# S01-INTERFACES.net
KiCad netlist of a schematic drawn in Altium Designer
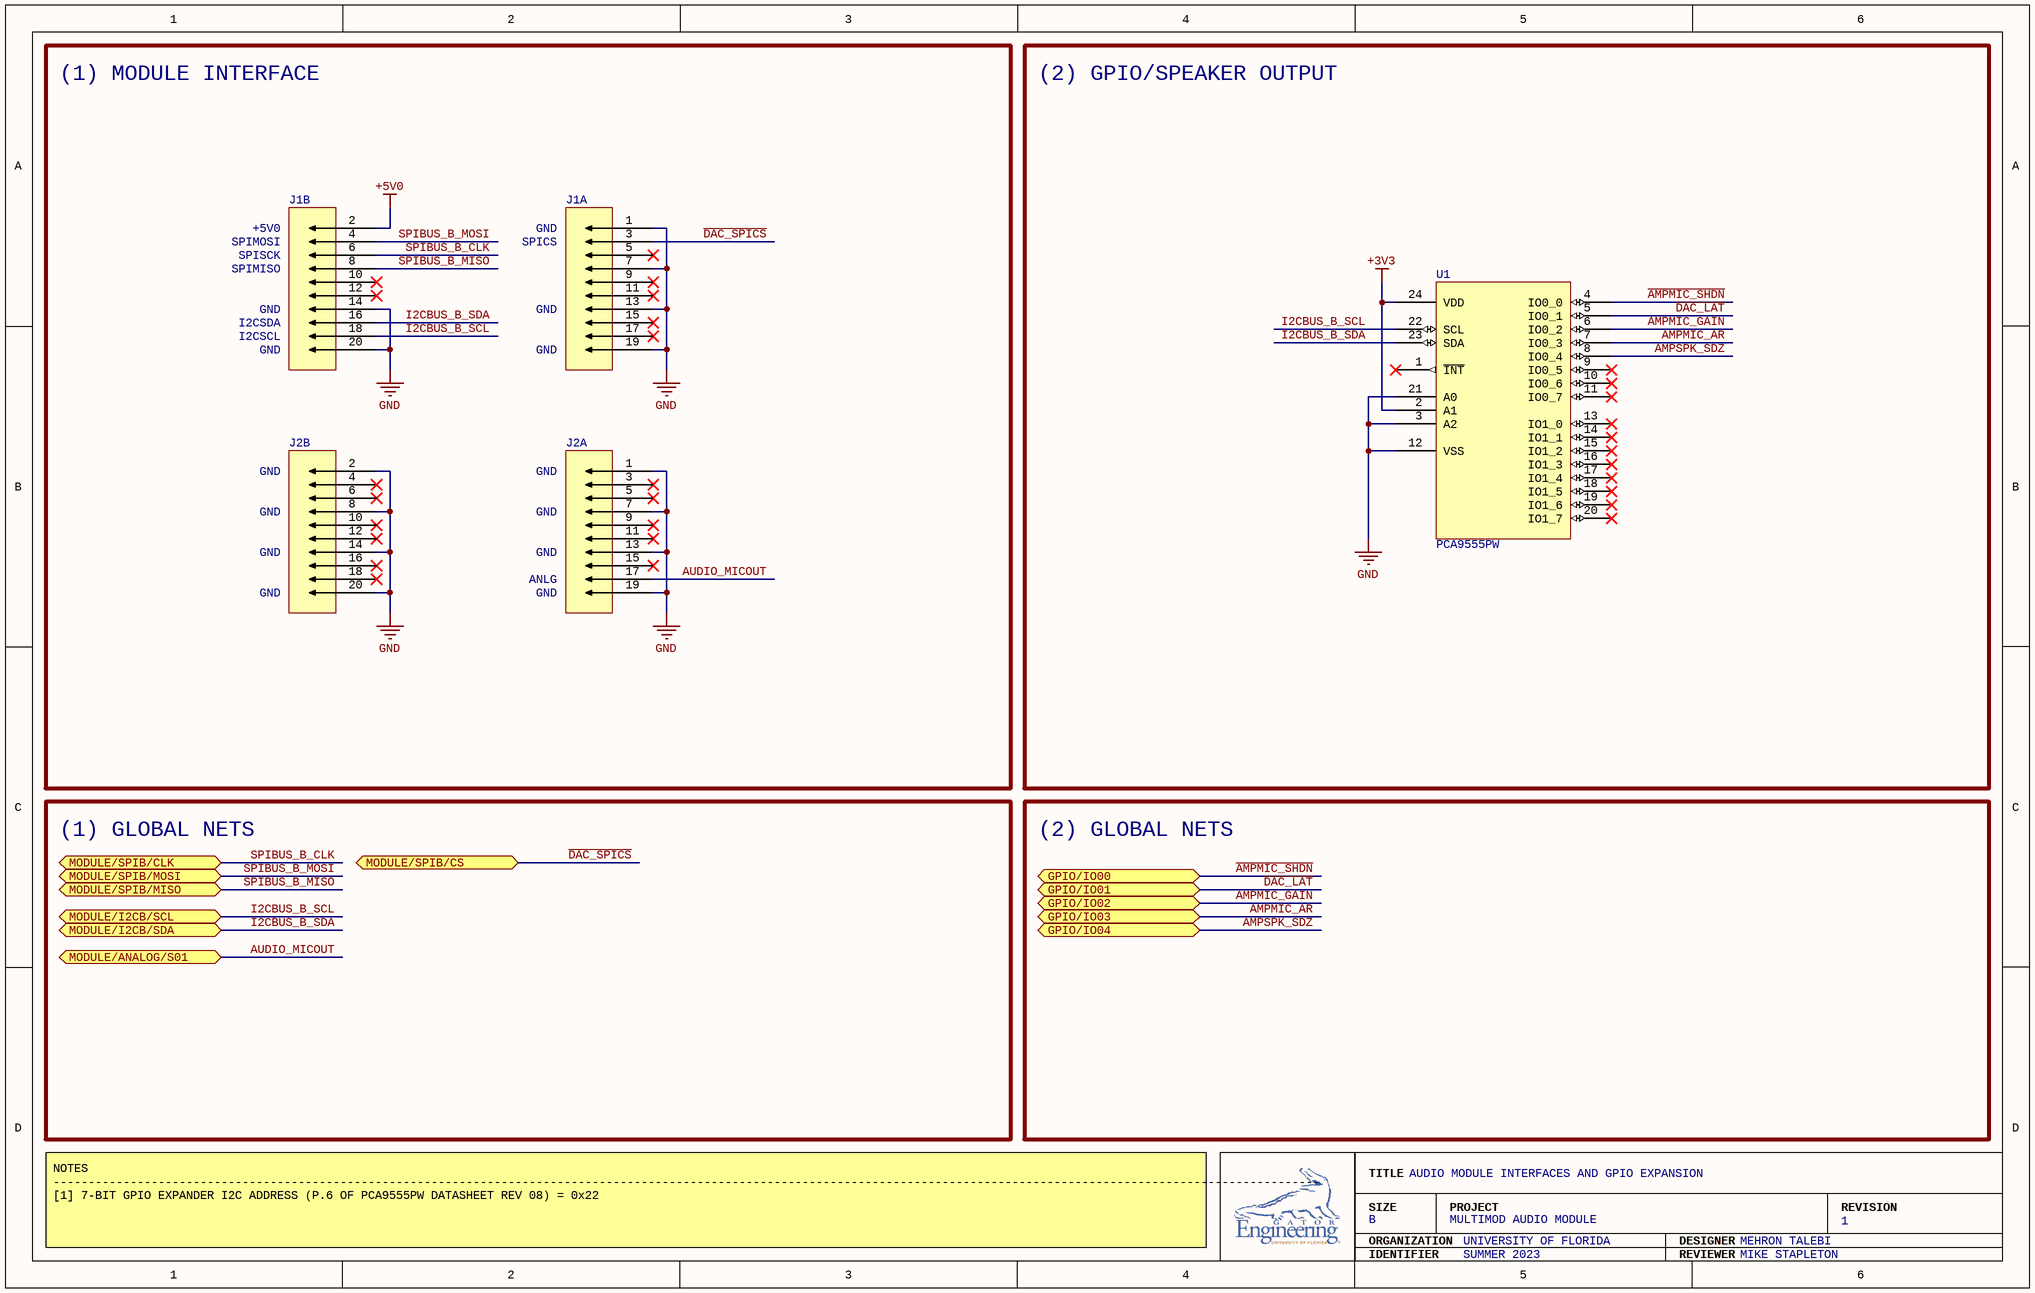
[diagram p0: S01-INTERFACES.SchDoc]

(export (version "E")
  (design (tool "Eeschema 10.0.6"))
  (components
    (comp (ref "J1")
      (value "NPTC102KFMS-RC")
      (footprint "NPTC102KFMS-RC")
      (description "CONN HDR 20POS 0.1 TIN SMD")
      (libsource (lib "Master") (part "NPTC102KFMS-RC"))
    )
    (comp (ref "J2")
      (value "NPTC102KFMS-RC")
      (footprint "NPTC102KFMS-RC")
      (description "CONN HDR 20POS 0.1 TIN SMD")
      (libsource (lib "Master") (part "NPTC102KFMS-RC"))
    )
    (comp (ref "U1")
      (value "PCA9555PW")
      (footprint "PCA9555PW")
      (description "IC XPND 400KHZ I2C SMBUS 24TSSOP")
      (libsource (lib "Master") (part "PCA9555PW"))
    )
  )
  (nets
    (net (code "1") (name "+3V3") (class "Default")
      (node (ref "U1") (pin "2") (pinfunction "A1_2") (pintype "passive"))
      (node (ref "U1") (pin "24") (pinfunction "VDD_24") (pintype "power_in"))
    )
    (net (code "2") (name "+5V0") (class "Default")
      (node (ref "J1") (pin "2") (pinfunction "2_2") (pintype "passive"))
    )
    (net (code "3") (name "/AMPMIC_AR") (class "Default")
      (node (ref "U1") (pin "7") (pinfunction "IO0_3_7") (pintype "bidirectional"))
    )
    (net (code "4") (name "/AMPMIC_GAIN") (class "Default")
      (node (ref "U1") (pin "6") (pinfunction "IO0_2_6") (pintype "bidirectional"))
    )
    (net (code "5") (name "/AMPMIC_SHDN") (class "Default")
      (node (ref "U1") (pin "4") (pinfunction "IO0_0_4") (pintype "bidirectional"))
    )
    (net (code "6") (name "/AMPSPK_SDZ") (class "Default")
      (node (ref "U1") (pin "8") (pinfunction "IO0_4_8") (pintype "bidirectional"))
    )
    (net (code "7") (name "/AUDIO_MICOUT") (class "Default")
      (node (ref "J2") (pin "17") (pinfunction "17_17") (pintype "passive"))
    )
    (net (code "8") (name "/DAC_LAT") (class "Default")
      (node (ref "U1") (pin "5") (pinfunction "IO0_1_5") (pintype "bidirectional"))
    )
    (net (code "9") (name "/DAC_SPICS") (class "Default")
      (node (ref "J1") (pin "3") (pinfunction "3_3") (pintype "passive"))
    )
    (net (code "10") (name "/I2CBUS_B_SCL") (class "Default")
      (node (ref "J1") (pin "18") (pinfunction "18_18") (pintype "passive"))
      (node (ref "U1") (pin "22") (pinfunction "SCL_22") (pintype "bidirectional"))
    )
    (net (code "11") (name "/I2CBUS_B_SDA") (class "Default")
      (node (ref "J1") (pin "16") (pinfunction "16_16") (pintype "passive"))
      (node (ref "U1") (pin "23") (pinfunction "SDA_23") (pintype "bidirectional"))
    )
    (net (code "12") (name "/SPIBUS_B_CLK") (class "Default")
      (node (ref "J1") (pin "6") (pinfunction "6_6") (pintype "passive"))
    )
    (net (code "13") (name "/SPIBUS_B_MISO") (class "Default")
      (node (ref "J1") (pin "8") (pinfunction "8_8") (pintype "passive"))
    )
    (net (code "14") (name "/SPIBUS_B_MOSI") (class "Default")
      (node (ref "J1") (pin "4") (pinfunction "4_4") (pintype "passive"))
    )
    (net (code "15") (name "GND") (class "Default")
      (node (ref "J1") (pin "1") (pinfunction "1_1") (pintype "passive"))
      (node (ref "J1") (pin "13") (pinfunction "13_13") (pintype "passive"))
      (node (ref "J1") (pin "14") (pinfunction "14_14") (pintype "passive"))
      (node (ref "J1") (pin "19") (pinfunction "19_19") (pintype "passive"))
      (node (ref "J1") (pin "20") (pinfunction "20_20") (pintype "passive"))
      (node (ref "J1") (pin "7") (pinfunction "7_7") (pintype "passive"))
      (node (ref "J2") (pin "1") (pinfunction "1_1") (pintype "passive"))
      (node (ref "J2") (pin "13") (pinfunction "13_13") (pintype "passive"))
      (node (ref "J2") (pin "14") (pinfunction "14_14") (pintype "passive"))
      (node (ref "J2") (pin "19") (pinfunction "19_19") (pintype "passive"))
      (node (ref "J2") (pin "2") (pinfunction "2_2") (pintype "passive"))
      (node (ref "J2") (pin "20") (pinfunction "20_20") (pintype "passive"))
      (node (ref "J2") (pin "7") (pinfunction "7_7") (pintype "passive"))
      (node (ref "J2") (pin "8") (pinfunction "8_8") (pintype "passive"))
      (node (ref "U1") (pin "12") (pinfunction "VSS_12") (pintype "power_in"))
      (node (ref "U1") (pin "21") (pinfunction "A0_21") (pintype "passive"))
      (node (ref "U1") (pin "3") (pinfunction "A2_3") (pintype "passive"))
    )
    (net (code "16") (name "unconnected-(J1-Pad5)") (class "Default")
      (node (ref "J1") (pin "5") (pinfunction "5_5") (pintype "passive+no_connect"))
    )
    (net (code "17") (name "unconnected-(J1-Pad9)") (class "Default")
      (node (ref "J1") (pin "9") (pinfunction "9_9") (pintype "passive+no_connect"))
    )
    (net (code "18") (name "unconnected-(J1-Pad10)") (class "Default")
      (node (ref "J1") (pin "10") (pinfunction "10_10") (pintype "passive+no_connect"))
    )
    (net (code "19") (name "unconnected-(J1-Pad11)") (class "Default")
      (node (ref "J1") (pin "11") (pinfunction "11_11") (pintype "passive+no_connect"))
    )
    (net (code "20") (name "unconnected-(J1-Pad12)") (class "Default")
      (node (ref "J1") (pin "12") (pinfunction "12_12") (pintype "passive+no_connect"))
    )
    (net (code "21") (name "unconnected-(J1-Pad15)") (class "Default")
      (node (ref "J1") (pin "15") (pinfunction "15_15") (pintype "passive+no_connect"))
    )
    (net (code "22") (name "unconnected-(J1-Pad17)") (class "Default")
      (node (ref "J1") (pin "17") (pinfunction "17_17") (pintype "passive+no_connect"))
    )
    (net (code "23") (name "unconnected-(J2-Pad3)") (class "Default")
      (node (ref "J2") (pin "3") (pinfunction "3_3") (pintype "passive+no_connect"))
    )
    (net (code "24") (name "unconnected-(J2-Pad4)") (class "Default")
      (node (ref "J2") (pin "4") (pinfunction "4_4") (pintype "passive+no_connect"))
    )
    (net (code "25") (name "unconnected-(J2-Pad5)") (class "Default")
      (node (ref "J2") (pin "5") (pinfunction "5_5") (pintype "passive+no_connect"))
    )
    (net (code "26") (name "unconnected-(J2-Pad6)") (class "Default")
      (node (ref "J2") (pin "6") (pinfunction "6_6") (pintype "passive+no_connect"))
    )
    (net (code "27") (name "unconnected-(J2-Pad9)") (class "Default")
      (node (ref "J2") (pin "9") (pinfunction "9_9") (pintype "passive+no_connect"))
    )
    (net (code "28") (name "unconnected-(J2-Pad10)") (class "Default")
      (node (ref "J2") (pin "10") (pinfunction "10_10") (pintype "passive+no_connect"))
    )
    (net (code "29") (name "unconnected-(J2-Pad11)") (class "Default")
      (node (ref "J2") (pin "11") (pinfunction "11_11") (pintype "passive+no_connect"))
    )
    (net (code "30") (name "unconnected-(J2-Pad12)") (class "Default")
      (node (ref "J2") (pin "12") (pinfunction "12_12") (pintype "passive+no_connect"))
    )
    (net (code "31") (name "unconnected-(J2-Pad15)") (class "Default")
      (node (ref "J2") (pin "15") (pinfunction "15_15") (pintype "passive+no_connect"))
    )
    (net (code "32") (name "unconnected-(J2-Pad16)") (class "Default")
      (node (ref "J2") (pin "16") (pinfunction "16_16") (pintype "passive+no_connect"))
    )
    (net (code "33") (name "unconnected-(J2-Pad18)") (class "Default")
      (node (ref "J2") (pin "18") (pinfunction "18_18") (pintype "passive+no_connect"))
    )
    (net (code "34") (name "unconnected-(U1-INT-Pad1)") (class "Default")
      (node (ref "U1") (pin "1") (pinfunction "INT_1") (pintype "output+no_connect"))
    )
    (net (code "35") (name "unconnected-(U1-IO0_5-Pad9)") (class "Default")
      (node (ref "U1") (pin "9") (pinfunction "IO0_5_9") (pintype "bidirectional+no_connect"))
    )
    (net (code "36") (name "unconnected-(U1-IO0_6-Pad10)") (class "Default")
      (node (ref "U1") (pin "10") (pinfunction "IO0_6_10") (pintype "bidirectional+no_connect"))
    )
    (net (code "37") (name "unconnected-(U1-IO0_7-Pad11)") (class "Default")
      (node (ref "U1") (pin "11") (pinfunction "IO0_7_11") (pintype "bidirectional+no_connect"))
    )
    (net (code "38") (name "unconnected-(U1-IO1_0-Pad13)") (class "Default")
      (node (ref "U1") (pin "13") (pinfunction "IO1_0_13") (pintype "bidirectional+no_connect"))
    )
    (net (code "39") (name "unconnected-(U1-IO1_1-Pad14)") (class "Default")
      (node (ref "U1") (pin "14") (pinfunction "IO1_1_14") (pintype "bidirectional+no_connect"))
    )
    (net (code "40") (name "unconnected-(U1-IO1_2-Pad15)") (class "Default")
      (node (ref "U1") (pin "15") (pinfunction "IO1_2_15") (pintype "bidirectional+no_connect"))
    )
    (net (code "41") (name "unconnected-(U1-IO1_3-Pad16)") (class "Default")
      (node (ref "U1") (pin "16") (pinfunction "IO1_3_16") (pintype "bidirectional+no_connect"))
    )
    (net (code "42") (name "unconnected-(U1-IO1_4-Pad17)") (class "Default")
      (node (ref "U1") (pin "17") (pinfunction "IO1_4_17") (pintype "bidirectional+no_connect"))
    )
    (net (code "43") (name "unconnected-(U1-IO1_5-Pad18)") (class "Default")
      (node (ref "U1") (pin "18") (pinfunction "IO1_5_18") (pintype "bidirectional+no_connect"))
    )
    (net (code "44") (name "unconnected-(U1-IO1_6-Pad19)") (class "Default")
      (node (ref "U1") (pin "19") (pinfunction "IO1_6_19") (pintype "bidirectional+no_connect"))
    )
    (net (code "45") (name "unconnected-(U1-IO1_7-Pad20)") (class "Default")
      (node (ref "U1") (pin "20") (pinfunction "IO1_7_20") (pintype "bidirectional+no_connect"))
    )
  )
)
